# 60K.net
KiCad netlist of a schematic drawn in Altium Designer
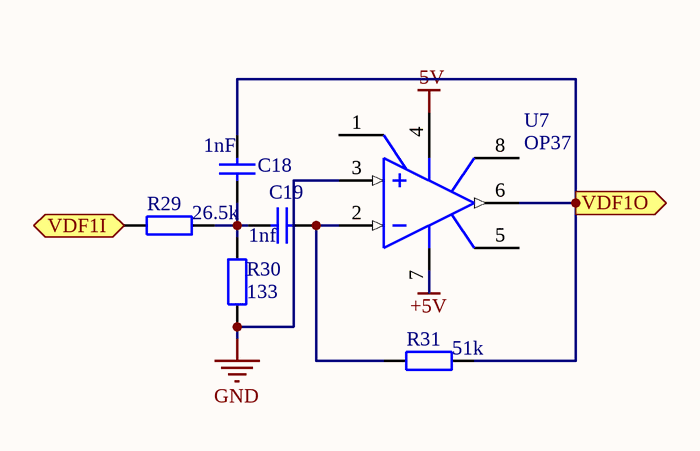
[diagram p0: 窄带滤波60K.SchDoc]

(export (version "E")
  (design (tool "Eeschema 10.0.6"))
  (components
    (comp (ref "C18")
      (value "瓷片电容")
      (footprint "瓷片电容")
      (fields (field (name "ALTIUM_UNNAMED_1") "1nF"))
      (libsource (lib "自制库（原理图文件）") (part "瓷片电容"))
    )
    (comp (ref "C19")
      (value "瓷片电容")
      (footprint "瓷片电容")
      (fields (field (name "ALTIUM_UNNAMED_1") "1nf"))
      (libsource (lib "自制库（原理图文件）") (part "瓷片电容"))
    )
    (comp (ref "R29")
      (value "26.5k")
      (footprint "AXIAL-0.4")
      (description "Resistor")
      (fields (field (name "Comment") "Res2") (field (name "PUBLISHER") "Altium Limited"))
      (libsource (lib "") (part "Res2_1"))
    )
    (comp (ref "R30")
      (value "133")
      (footprint "AXIAL-0.4")
      (description "Resistor")
      (fields (field (name "Comment") "Res2") (field (name "PUBLISHER") "Altium Limited"))
      (libsource (lib "Miscellaneous Devices") (part "Res2"))
    )
    (comp (ref "R31")
      (value "51k")
      (footprint "AXIAL-0.4")
      (description "Resistor")
      (fields (field (name "Comment") "Res2") (field (name "PUBLISHER") "Altium Limited"))
      (libsource (lib "") (part "Res2_1"))
    )
    (comp (ref "U7")
      (value "OP37")
      (footprint "N-8_A")
      (description "Ultra-Low Offset Voltage Operational Amplifier")
      (fields (field (name "PUBLISHER") "Altium Limited"))
      (libsource (lib "AD Operational Amplifier") (part "ADOP07CN"))
    )
  )
  (nets
    (net (code "1") (name "+5V") (class "Default")
      (node (ref "U7") (pin "7") (pinfunction "V+_7") (pintype "power_in"))
    )
    (net (code "2") (name "-5V") (class "Default")
      (node (ref "U7") (pin "4") (pinfunction "V-_4") (pintype "power_in"))
    )
    (net (code "3") (name "/VDF1I") (class "Default")
      (node (ref "R29") (pin "1") (pinfunction "1_1") (pintype "passive"))
    )
    (net (code "4") (name "/VDF1O") (class "Default")
      (node (ref "C18") (pin "1") (pinfunction "1_1") (pintype "passive"))
      (node (ref "R31") (pin "2") (pinfunction "2_2") (pintype "passive"))
      (node (ref "U7") (pin "6") (pinfunction "OUT_6") (pintype "output"))
    )
    (net (code "5") (name "GND") (class "Default")
      (node (ref "R30") (pin "1") (pinfunction "1_1") (pintype "passive"))
      (node (ref "U7") (pin "3") (pinfunction "IN+_3") (pintype "input"))
    )
    (net (code "6") (name "Net-(C18-Pad2)") (class "Default")
      (node (ref "C18") (pin "2") (pinfunction "2_2") (pintype "passive"))
      (node (ref "C19") (pin "2") (pinfunction "2_2") (pintype "passive"))
      (node (ref "R29") (pin "2") (pinfunction "2_2") (pintype "passive"))
      (node (ref "R30") (pin "2") (pinfunction "2_2") (pintype "passive"))
    )
    (net (code "7") (name "Net-(U7-IN-)") (class "Default")
      (node (ref "C19") (pin "1") (pinfunction "1_1") (pintype "passive"))
      (node (ref "R31") (pin "1") (pinfunction "1_1") (pintype "passive"))
      (node (ref "U7") (pin "2") (pinfunction "IN-_2") (pintype "input"))
    )
    (net (code "8") (name "unconnected-(U7-NC-Pad5)") (class "Default")
      (node (ref "U7") (pin "5") (pinfunction "NC_5") (pintype "passive"))
    )
    (net (code "9") (name "unconnected-(U7-NULL1-Pad1)") (class "Default")
      (node (ref "U7") (pin "1") (pinfunction "NULL1_1") (pintype "passive"))
    )
    (net (code "10") (name "unconnected-(U7-NULL2-Pad8)") (class "Default")
      (node (ref "U7") (pin "8") (pinfunction "NULL2_8") (pintype "passive"))
    )
  )
)
